# RetroAdapter2CommonGround.net
KiCad netlist of a schematic drawn in EAGLE
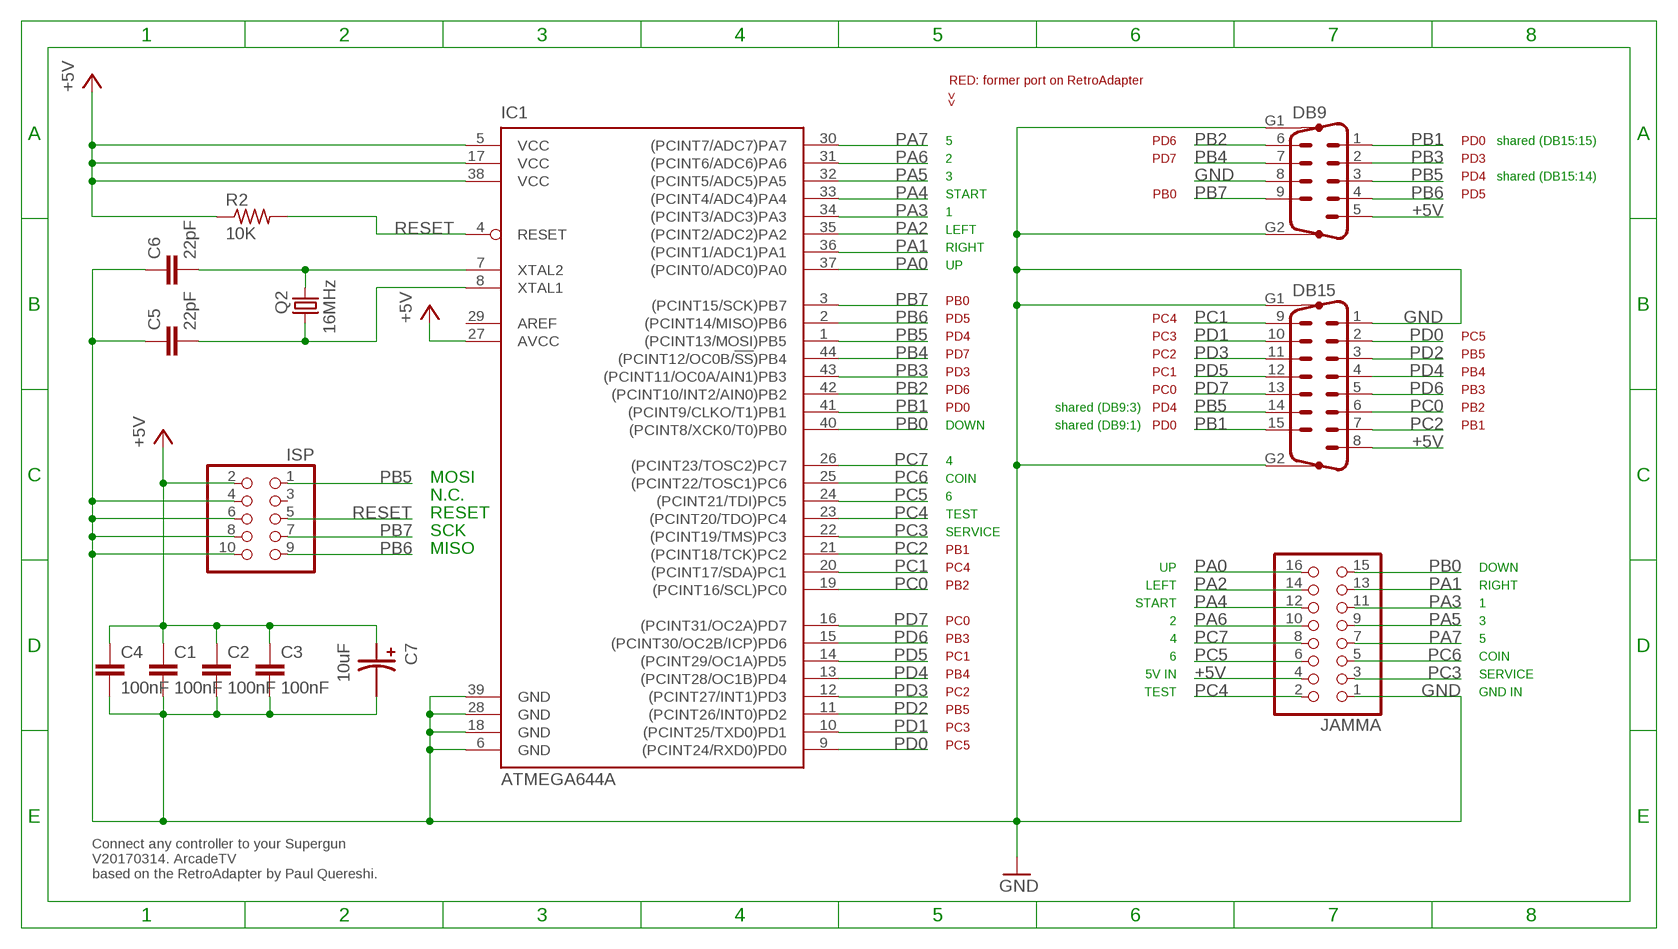
[diagram p0: schematic, sheet 1]

(export (version "E")
  (design (tool "Eeschema 10.0.6"))
  (components
    (comp (ref "C1")
      (value "100nF")
      (footprint "eagle-import:Z0805")
      (libsource (lib "eagle-import") (part "C0805"))
    )
    (comp (ref "C2")
      (value "100nF")
      (footprint "eagle-import:Z0805")
      (libsource (lib "eagle-import") (part "C0805"))
    )
    (comp (ref "C3")
      (value "100nF")
      (footprint "eagle-import:Z0805")
      (libsource (lib "eagle-import") (part "C0805"))
    )
    (comp (ref "C4")
      (value "100nF")
      (footprint "eagle-import:Z0805")
      (libsource (lib "eagle-import") (part "C0805"))
    )
    (comp (ref "C5")
      (value "22pF")
      (footprint "eagle-import:Z0805")
      (libsource (lib "eagle-import") (part "C0805"))
    )
    (comp (ref "C6")
      (value "22pF")
      (footprint "eagle-import:Z0805")
      (libsource (lib "eagle-import") (part "C0805"))
    )
    (comp (ref "C7")
      (value "10uF")
      (footprint "eagle-import:EEEFPJ101UAR_PANASONIC_VFP-SERIES")
      (libsource (lib "eagle-import") (part "EEEFPJ101UAR_PANASONIC_VFP-SERIES"))
    )
    (comp (ref "DB9")
      (value "M09HP")
      (footprint "eagle-import:M09HP")
      (libsource (lib "eagle-import") (part "M09HP"))
    )
    (comp (ref "DB15")
      (value "M15HP")
      (footprint "eagle-import:M15HP")
      (libsource (lib "eagle-import") (part "M15HP"))
    )
    (comp (ref "IC1")
      (value "ATMEGA644A")
      (footprint "eagle-import:TQFP44")
      (fields (field (name "MPN") "ATMEGA644PV-10AU"))
      (libsource (lib "eagle-import") (part "ATMEGA644A"))
    )
    (comp (ref "ISP")
      (value "PINHD-2X5")
      (footprint "eagle-import:2X05")
      (libsource (lib "eagle-import") (part "PINHD-2X5"))
    )
    (comp (ref "JAMMA")
      (value "PINHD-2X8")
      (footprint "eagle-import:2X08")
      (libsource (lib "eagle-import") (part "PINHD-2X8"))
    )
    (comp (ref "Q2")
      (value "16MHz")
      (footprint "eagle-import:HC49_S")
      (libsource (lib "eagle-import") (part "CRYSTALHC49S"))
    )
    (comp (ref "R2")
      (value "10K")
      (footprint "eagle-import:R0603")
      (libsource (lib "eagle-import") (part "R-US_R0603"))
    )
  )
  (nets
    (net (code "1") (name "+5V") (class "Default")
      (node (ref "C1") (pin "1") (pinfunction "1_1") (pintype "passive"))
      (node (ref "C2") (pin "1") (pinfunction "1_1") (pintype "passive"))
      (node (ref "C3") (pin "1") (pinfunction "1_1") (pintype "passive"))
      (node (ref "C4") (pin "1") (pinfunction "1_1") (pintype "passive"))
      (node (ref "C7") (pin "PLUS") (pinfunction "+_PLUS") (pintype "bidirectional"))
      (node (ref "DB15") (pin "8") (pinfunction "8_8") (pintype "passive"))
      (node (ref "DB9") (pin "5") (pinfunction "5_5") (pintype "passive"))
      (node (ref "IC1") (pin "17") (pinfunction "VCC_17") (pintype "power_in"))
      (node (ref "IC1") (pin "27") (pinfunction "AVCC_27") (pintype "power_in"))
      (node (ref "IC1") (pin "38") (pinfunction "VCC_38") (pintype "power_in"))
      (node (ref "IC1") (pin "5") (pinfunction "VCC_5") (pintype "power_in"))
      (node (ref "ISP") (pin "2") (pinfunction "2_2") (pintype "passive"))
      (node (ref "JAMMA") (pin "4") (pinfunction "4_4") (pintype "passive"))
      (node (ref "R2") (pin "1") (pinfunction "1_1") (pintype "passive"))
    )
    (net (code "2") (name "/PA0") (class "Default")
      (node (ref "IC1") (pin "37") (pinfunction "(PCINT0/ADC0)PA0_37") (pintype "bidirectional"))
      (node (ref "JAMMA") (pin "16") (pinfunction "16_16") (pintype "passive"))
    )
    (net (code "3") (name "/PA1") (class "Default")
      (node (ref "IC1") (pin "36") (pinfunction "(PCINT1/ADC1)PA1_36") (pintype "bidirectional"))
      (node (ref "JAMMA") (pin "13") (pinfunction "13_13") (pintype "passive"))
    )
    (net (code "4") (name "/PA2") (class "Default")
      (node (ref "IC1") (pin "35") (pinfunction "(PCINT2/ADC2)PA2_35") (pintype "bidirectional"))
      (node (ref "JAMMA") (pin "14") (pinfunction "14_14") (pintype "passive"))
    )
    (net (code "5") (name "/PA3") (class "Default")
      (node (ref "IC1") (pin "34") (pinfunction "(PCINT3/ADC3)PA3_34") (pintype "bidirectional"))
      (node (ref "JAMMA") (pin "11") (pinfunction "11_11") (pintype "passive"))
    )
    (net (code "6") (name "/PA4") (class "Default")
      (node (ref "IC1") (pin "33") (pinfunction "(PCINT4/ADC4)PA4_33") (pintype "bidirectional"))
      (node (ref "JAMMA") (pin "12") (pinfunction "12_12") (pintype "passive"))
    )
    (net (code "7") (name "/PA5") (class "Default")
      (node (ref "IC1") (pin "32") (pinfunction "(PCINT5/ADC5)PA5_32") (pintype "bidirectional"))
      (node (ref "JAMMA") (pin "9") (pinfunction "9_9") (pintype "passive"))
    )
    (net (code "8") (name "/PA6") (class "Default")
      (node (ref "IC1") (pin "31") (pinfunction "(PCINT6/ADC6)PA6_31") (pintype "bidirectional"))
      (node (ref "JAMMA") (pin "10") (pinfunction "10_10") (pintype "passive"))
    )
    (net (code "9") (name "/PA7") (class "Default")
      (node (ref "IC1") (pin "30") (pinfunction "(PCINT7/ADC7)PA7_30") (pintype "bidirectional"))
      (node (ref "JAMMA") (pin "7") (pinfunction "7_7") (pintype "passive"))
    )
    (net (code "10") (name "/PB0") (class "Default")
      (node (ref "IC1") (pin "40") (pinfunction "(PCINT8/XCK0/T0)PB0_40") (pintype "bidirectional"))
      (node (ref "JAMMA") (pin "15") (pinfunction "15_15") (pintype "passive"))
    )
    (net (code "11") (name "/PB1") (class "Default")
      (node (ref "DB15") (pin "15") (pinfunction "15_15") (pintype "passive"))
      (node (ref "DB9") (pin "1") (pinfunction "1_1") (pintype "passive"))
      (node (ref "IC1") (pin "41") (pinfunction "(PCINT9/CLKO/T1)PB1_41") (pintype "bidirectional"))
    )
    (net (code "12") (name "/PB2") (class "Default")
      (node (ref "DB9") (pin "6") (pinfunction "6_6") (pintype "passive"))
      (node (ref "IC1") (pin "42") (pinfunction "(PCINT10/INT2/AIN0)PB2_42") (pintype "bidirectional"))
    )
    (net (code "13") (name "/PB3") (class "Default")
      (node (ref "DB9") (pin "2") (pinfunction "2_2") (pintype "passive"))
      (node (ref "IC1") (pin "43") (pinfunction "(PCINT11/OC0A/AIN1)PB3_43") (pintype "bidirectional"))
    )
    (net (code "14") (name "/PB4") (class "Default")
      (node (ref "DB9") (pin "7") (pinfunction "7_7") (pintype "passive"))
      (node (ref "IC1") (pin "44") (pinfunction "(PCINT12/OC0B/~{SS})PB4_44") (pintype "bidirectional"))
    )
    (net (code "15") (name "/PB5") (class "Default")
      (node (ref "DB15") (pin "14") (pinfunction "14_14") (pintype "passive"))
      (node (ref "DB9") (pin "3") (pinfunction "3_3") (pintype "passive"))
      (node (ref "IC1") (pin "1") (pinfunction "(PCINT13/MOSI)PB5_1") (pintype "bidirectional"))
      (node (ref "ISP") (pin "1") (pinfunction "1_1") (pintype "passive"))
    )
    (net (code "16") (name "/PB6") (class "Default")
      (node (ref "DB9") (pin "4") (pinfunction "4_4") (pintype "passive"))
      (node (ref "IC1") (pin "2") (pinfunction "(PCINT14/MISO)PB6_2") (pintype "bidirectional"))
      (node (ref "ISP") (pin "9") (pinfunction "9_9") (pintype "passive"))
    )
    (net (code "17") (name "/PB7") (class "Default")
      (node (ref "DB9") (pin "9") (pinfunction "9_9") (pintype "passive"))
      (node (ref "IC1") (pin "3") (pinfunction "(PCINT15/SCK)PB7_3") (pintype "bidirectional"))
      (node (ref "ISP") (pin "7") (pinfunction "7_7") (pintype "passive"))
    )
    (net (code "18") (name "/PC0") (class "Default")
      (node (ref "DB15") (pin "6") (pinfunction "6_6") (pintype "passive"))
      (node (ref "IC1") (pin "19") (pinfunction "(PCINT16/SCL)PC0_19") (pintype "output"))
    )
    (net (code "19") (name "/PC1") (class "Default")
      (node (ref "DB15") (pin "9") (pinfunction "9_9") (pintype "passive"))
      (node (ref "IC1") (pin "20") (pinfunction "(PCINT17/SDA)PC1_20") (pintype "output"))
    )
    (net (code "20") (name "/PC2") (class "Default")
      (node (ref "DB15") (pin "7") (pinfunction "7_7") (pintype "passive"))
      (node (ref "IC1") (pin "21") (pinfunction "(PCINT18/TCK)PC2_21") (pintype "output"))
    )
    (net (code "21") (name "/PC3") (class "Default")
      (node (ref "IC1") (pin "22") (pinfunction "(PCINT19/TMS)PC3_22") (pintype "output"))
      (node (ref "JAMMA") (pin "3") (pinfunction "3_3") (pintype "passive"))
    )
    (net (code "22") (name "/PC4") (class "Default")
      (node (ref "IC1") (pin "23") (pinfunction "(PCINT20/TDO)PC4_23") (pintype "output"))
      (node (ref "JAMMA") (pin "2") (pinfunction "2_2") (pintype "passive"))
    )
    (net (code "23") (name "/PC5") (class "Default")
      (node (ref "IC1") (pin "24") (pinfunction "(PCINT21/TDI)PC5_24") (pintype "output"))
      (node (ref "JAMMA") (pin "6") (pinfunction "6_6") (pintype "passive"))
    )
    (net (code "24") (name "/PC6") (class "Default")
      (node (ref "IC1") (pin "25") (pinfunction "(PCINT22/TOSC1)PC6_25") (pintype "output"))
      (node (ref "JAMMA") (pin "5") (pinfunction "5_5") (pintype "passive"))
    )
    (net (code "25") (name "/PC7") (class "Default")
      (node (ref "IC1") (pin "26") (pinfunction "(PCINT23/TOSC2)PC7_26") (pintype "output"))
      (node (ref "JAMMA") (pin "8") (pinfunction "8_8") (pintype "passive"))
    )
    (net (code "26") (name "/PD0") (class "Default")
      (node (ref "DB15") (pin "2") (pinfunction "2_2") (pintype "passive"))
      (node (ref "IC1") (pin "9") (pinfunction "(PCINT24/RXD0)PD0_9") (pintype "bidirectional"))
    )
    (net (code "27") (name "/PD1") (class "Default")
      (node (ref "DB15") (pin "10") (pinfunction "10_10") (pintype "passive"))
      (node (ref "IC1") (pin "10") (pinfunction "(PCINT25/TXD0)PD1_10") (pintype "bidirectional"))
    )
    (net (code "28") (name "/PD2") (class "Default")
      (node (ref "DB15") (pin "3") (pinfunction "3_3") (pintype "passive"))
      (node (ref "IC1") (pin "11") (pinfunction "(PCINT26/INT0)PD2_11") (pintype "bidirectional"))
    )
    (net (code "29") (name "/PD3") (class "Default")
      (node (ref "DB15") (pin "11") (pinfunction "11_11") (pintype "passive"))
      (node (ref "IC1") (pin "12") (pinfunction "(PCINT27/INT1)PD3_12") (pintype "bidirectional"))
    )
    (net (code "30") (name "/PD4") (class "Default")
      (node (ref "DB15") (pin "4") (pinfunction "4_4") (pintype "passive"))
      (node (ref "IC1") (pin "13") (pinfunction "(PCINT28/OC1B)PD4_13") (pintype "bidirectional"))
    )
    (net (code "31") (name "/PD5") (class "Default")
      (node (ref "DB15") (pin "12") (pinfunction "12_12") (pintype "passive"))
      (node (ref "IC1") (pin "14") (pinfunction "(PCINT29/OC1A)PD5_14") (pintype "bidirectional"))
    )
    (net (code "32") (name "/PD6") (class "Default")
      (node (ref "DB15") (pin "5") (pinfunction "5_5") (pintype "passive"))
      (node (ref "IC1") (pin "15") (pinfunction "(PCINT30/OC2B/ICP)PD6_15") (pintype "bidirectional"))
    )
    (net (code "33") (name "/PD7") (class "Default")
      (node (ref "DB15") (pin "13") (pinfunction "13_13") (pintype "passive"))
      (node (ref "IC1") (pin "16") (pinfunction "(PCINT31/OC2A)PD7_16") (pintype "bidirectional"))
    )
    (net (code "34") (name "/RESET") (class "Default")
      (node (ref "IC1") (pin "4") (pinfunction "RESET_4") (pintype "input"))
      (node (ref "ISP") (pin "5") (pinfunction "5_5") (pintype "passive"))
      (node (ref "R2") (pin "2") (pinfunction "2_2") (pintype "passive"))
    )
    (net (code "35") (name "GND") (class "Default")
      (node (ref "C1") (pin "2") (pinfunction "2_2") (pintype "passive"))
      (node (ref "C2") (pin "2") (pinfunction "2_2") (pintype "passive"))
      (node (ref "C3") (pin "2") (pinfunction "2_2") (pintype "passive"))
      (node (ref "C4") (pin "2") (pinfunction "2_2") (pintype "passive"))
      (node (ref "C5") (pin "1") (pinfunction "1_1") (pintype "passive"))
      (node (ref "C6") (pin "1") (pinfunction "1_1") (pintype "passive"))
      (node (ref "C7") (pin "MINUS") (pinfunction "-_MINUS") (pintype "bidirectional"))
      (node (ref "DB15") (pin "1") (pinfunction "1_1") (pintype "passive"))
      (node (ref "DB15") (pin "G1") (pinfunction "G1_G1") (pintype "passive"))
      (node (ref "DB15") (pin "G2") (pinfunction "G2_G2") (pintype "passive"))
      (node (ref "DB9") (pin "8") (pinfunction "8_8") (pintype "passive"))
      (node (ref "DB9") (pin "G1") (pinfunction "G1_G1") (pintype "passive"))
      (node (ref "DB9") (pin "G2") (pinfunction "G2_G2") (pintype "passive"))
      (node (ref "IC1") (pin "18") (pinfunction "GND_18") (pintype "power_in"))
      (node (ref "IC1") (pin "28") (pinfunction "GND_28") (pintype "power_in"))
      (node (ref "IC1") (pin "39") (pinfunction "GND_39") (pintype "power_in"))
      (node (ref "IC1") (pin "6") (pinfunction "GND_6") (pintype "power_in"))
      (node (ref "ISP") (pin "10") (pinfunction "10_10") (pintype "passive"))
      (node (ref "ISP") (pin "4") (pinfunction "4_4") (pintype "passive"))
      (node (ref "ISP") (pin "6") (pinfunction "6_6") (pintype "passive"))
      (node (ref "ISP") (pin "8") (pinfunction "8_8") (pintype "passive"))
      (node (ref "JAMMA") (pin "1") (pinfunction "1_1") (pintype "passive"))
    )
    (net (code "36") (name "Net-(IC1-XTAL1)") (class "Default")
      (node (ref "C5") (pin "2") (pinfunction "2_2") (pintype "passive"))
      (node (ref "IC1") (pin "8") (pinfunction "XTAL1_8") (pintype "bidirectional"))
      (node (ref "Q2") (pin "1") (pinfunction "1_1") (pintype "passive"))
    )
    (net (code "37") (name "Net-(IC1-XTAL2)") (class "Default")
      (node (ref "C6") (pin "2") (pinfunction "2_2") (pintype "passive"))
      (node (ref "IC1") (pin "7") (pinfunction "XTAL2_7") (pintype "bidirectional"))
      (node (ref "Q2") (pin "2") (pinfunction "2_2") (pintype "passive"))
    )
    (net (code "38") (name "unconnected-(IC1-AREF-Pad29)") (class "Default")
      (node (ref "IC1") (pin "29") (pinfunction "AREF_29") (pintype "passive"))
    )
    (net (code "39") (name "unconnected-(ISP-Pad3)") (class "Default")
      (node (ref "ISP") (pin "3") (pinfunction "3_3") (pintype "passive"))
    )
  )
)
